# resonant-bpf-rev3.net
KiCad netlist of a schematic drawn in EAGLE
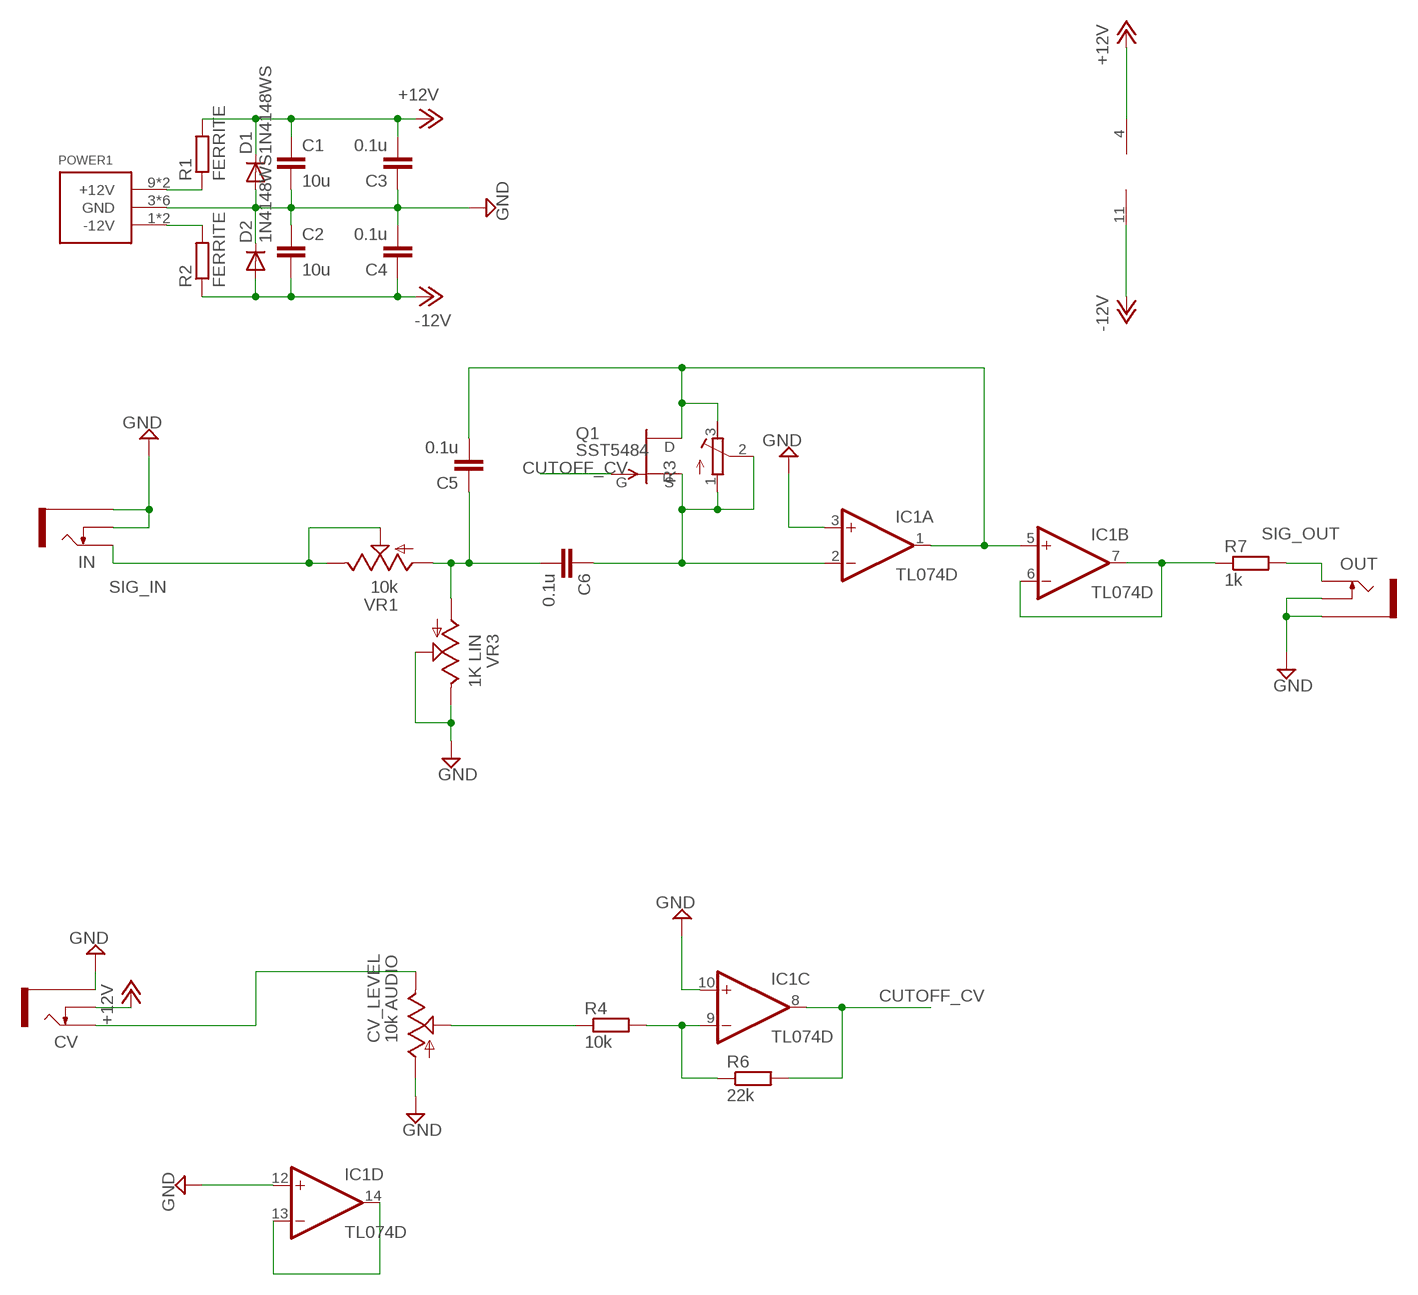
[diagram p0: schematic, sheet 1]

(export (version "E")
  (design (tool "Eeschema 10.0.6"))
  (components
    (comp (ref "C1")
      (value "10u")
      (footprint "eagle-import:C0805")
      (libsource (lib "eagle-import") (part "C-EUC0805"))
    )
    (comp (ref "C2")
      (value "10u")
      (footprint "eagle-import:C0805")
      (libsource (lib "eagle-import") (part "C-EUC0805"))
    )
    (comp (ref "C3")
      (value "0.1u")
      (footprint "eagle-import:C0805")
      (libsource (lib "eagle-import") (part "C-EUC0805"))
    )
    (comp (ref "C4")
      (value "0.1u")
      (footprint "eagle-import:C0805")
      (libsource (lib "eagle-import") (part "C-EUC0805"))
    )
    (comp (ref "C5")
      (value "0.1u")
      (footprint "eagle-import:C0805")
      (libsource (lib "eagle-import") (part "C-EUC0805"))
    )
    (comp (ref "C6")
      (value "0.1u")
      (footprint "eagle-import:C0805")
      (libsource (lib "eagle-import") (part "C-EUC0805"))
    )
    (comp (ref "CV")
      (value "THONKICONNNEW")
      (footprint "eagle-import:WQP-PJ301M-12_JACK")
      (libsource (lib "eagle-import") (part "THONKICONNNEW"))
    )
    (comp (ref "CV_LEVEL")
      (value "10k AUDIO")
      (footprint "eagle-import:9MM_SNAP-IN_POT")
      (libsource (lib "eagle-import") (part "9MM_SNAP-IN_POT_"))
    )
    (comp (ref "D1")
      (value "1N4148WS")
      (footprint "eagle-import:SOD323-W")
      (libsource (lib "eagle-import") (part "DIODE-SOD323-W"))
    )
    (comp (ref "D2")
      (value "1N4148WS")
      (footprint "eagle-import:SOD323-W")
      (libsource (lib "eagle-import") (part "DIODE-SOD323-W"))
    )
    (comp (ref "IC1")
      (value "TL074D")
      (footprint "eagle-import:SO14")
      (libsource (lib "eagle-import") (part "TL074D"))
    )
    (comp (ref "IN")
      (value "THONKICONNNEW")
      (footprint "eagle-import:WQP-PJ301M-12_JACK")
      (libsource (lib "eagle-import") (part "THONKICONNNEW"))
    )
    (comp (ref "OUT")
      (value "THONKICONNNEW")
      (footprint "eagle-import:WQP-PJ301M-12_JACK")
      (libsource (lib "eagle-import") (part "THONKICONNNEW"))
    )
    (comp (ref "POWER1")
      (value "POWER_SIMPLE10")
      (footprint "eagle-import:POWER_10")
      (libsource (lib "eagle-import") (part "POWER_SIMPLE10"))
    )
    (comp (ref "Q1")
      (value "SST5484")
      (footprint "eagle-import:SOT23")
      (libsource (lib "eagle-import") (part "?548SST4"))
    )
    (comp (ref "R1")
      (value "FERRITE")
      (footprint "eagle-import:R0805")
      (libsource (lib "eagle-import") (part "R-EU_R0805"))
    )
    (comp (ref "R2")
      (value "FERRITE")
      (footprint "eagle-import:R0805")
      (libsource (lib "eagle-import") (part "R-EU_R0805"))
    )
    (comp (ref "R3")
      (value "R-TRIMM3296W")
      (footprint "eagle-import:RTRIM3296W")
      (libsource (lib "eagle-import") (part "R-TRIMM3296W"))
    )
    (comp (ref "R4")
      (value "10k")
      (footprint "eagle-import:R0805")
      (libsource (lib "eagle-import") (part "R-EU_R0805"))
    )
    (comp (ref "R6")
      (value "22k")
      (footprint "eagle-import:R0805")
      (libsource (lib "eagle-import") (part "R-EU_R0805"))
    )
    (comp (ref "R7")
      (value "1k")
      (footprint "eagle-import:R0805")
      (libsource (lib "eagle-import") (part "R-EU_R0805"))
    )
    (comp (ref "VR1")
      (value "10k")
      (footprint "eagle-import:9MM_SNAP-IN_POT")
      (libsource (lib "eagle-import") (part "9MM_SNAP-IN_POT_"))
    )
    (comp (ref "VR3")
      (value "1K LIN")
      (footprint "eagle-import:9MM_SNAP-IN_POT")
      (libsource (lib "eagle-import") (part "9MM_SNAP-IN_POT_"))
    )
  )
  (nets
    (net (code "1") (name "+12V") (class "Default")
      (node (ref "C1") (pin "1") (pinfunction "1_1") (pintype "passive"))
      (node (ref "C3") (pin "2") (pinfunction "2_2") (pintype "passive"))
      (node (ref "CV") (pin "P$2_SWITCH") (pinfunction "SWITCH_P$2_SWITCH") (pintype "passive"))
      (node (ref "D1") (pin "C") (pinfunction "C_C") (pintype "passive"))
      (node (ref "IC1") (pin "4") (pinfunction "V+_4") (pintype "power_in"))
      (node (ref "R1") (pin "2") (pinfunction "2_2") (pintype "passive"))
    )
    (net (code "2") (name "-12V") (class "Default")
      (node (ref "C2") (pin "2") (pinfunction "2_2") (pintype "passive"))
      (node (ref "C4") (pin "1") (pinfunction "1_1") (pintype "passive"))
      (node (ref "D2") (pin "A") (pinfunction "A_A") (pintype "passive"))
      (node (ref "IC1") (pin "11") (pinfunction "V-_11") (pintype "power_in"))
      (node (ref "R2") (pin "1") (pinfunction "1_1") (pintype "passive"))
    )
    (net (code "3") (name "/CUTOFF_CV") (class "Default")
      (node (ref "IC1") (pin "8") (pinfunction "OUT_8") (pintype "output"))
      (node (ref "Q1") (pin "3") (pinfunction "G_3") (pintype "passive"))
      (node (ref "R6") (pin "2") (pinfunction "2_2") (pintype "passive"))
    )
    (net (code "4") (name "/SIG_IN") (class "Default")
      (node (ref "IN") (pin "P$1_TIP") (pinfunction "TIP_P$1_TIP") (pintype "passive"))
      (node (ref "VR1") (pin "2") (pinfunction "S_2") (pintype "passive"))
      (node (ref "VR1") (pin "3") (pinfunction "E_3") (pintype "passive"))
    )
    (net (code "5") (name "/SIG_OUT") (class "Default")
      (node (ref "OUT") (pin "P$1_TIP") (pinfunction "TIP_P$1_TIP") (pintype "passive"))
      (node (ref "R7") (pin "2") (pinfunction "2_2") (pintype "passive"))
    )
    (net (code "6") (name "GND") (class "Default")
      (node (ref "C1") (pin "2") (pinfunction "2_2") (pintype "passive"))
      (node (ref "C2") (pin "1") (pinfunction "1_1") (pintype "passive"))
      (node (ref "C3") (pin "1") (pinfunction "1_1") (pintype "passive"))
      (node (ref "C4") (pin "2") (pinfunction "2_2") (pintype "passive"))
      (node (ref "CV") (pin "P$3_SLEEVE") (pinfunction "SLEEVE_P$3_SLEEVE") (pintype "passive"))
      (node (ref "CV_LEVEL") (pin "1") (pinfunction "A_1") (pintype "passive"))
      (node (ref "D1") (pin "A") (pinfunction "A_A") (pintype "passive"))
      (node (ref "D2") (pin "C") (pinfunction "C_C") (pintype "passive"))
      (node (ref "IC1") (pin "10") (pinfunction "+IN_10") (pintype "input"))
      (node (ref "IC1") (pin "12") (pinfunction "+IN_12") (pintype "input"))
      (node (ref "IC1") (pin "3") (pinfunction "+IN_3") (pintype "input"))
      (node (ref "IN") (pin "P$2_SWITCH") (pinfunction "SWITCH_P$2_SWITCH") (pintype "passive"))
      (node (ref "IN") (pin "P$3_SLEEVE") (pinfunction "SLEEVE_P$3_SLEEVE") (pintype "passive"))
      (node (ref "OUT") (pin "P$2_SWITCH") (pinfunction "SWITCH_P$2_SWITCH") (pintype "passive"))
      (node (ref "OUT") (pin "P$3_SLEEVE") (pinfunction "SLEEVE_P$3_SLEEVE") (pintype "passive"))
      (node (ref "POWER1") (pin "3") (pinfunction "GND_3") (pintype "bidirectional"))
      (node (ref "POWER1") (pin "4") (pinfunction "GND_4") (pintype "bidirectional"))
      (node (ref "POWER1") (pin "5") (pinfunction "GND_5") (pintype "bidirectional"))
      (node (ref "POWER1") (pin "6") (pinfunction "GND_6") (pintype "bidirectional"))
      (node (ref "POWER1") (pin "7") (pinfunction "GND_7") (pintype "bidirectional"))
      (node (ref "POWER1") (pin "8") (pinfunction "GND_8") (pintype "bidirectional"))
      (node (ref "VR3") (pin "2") (pinfunction "S_2") (pintype "passive"))
      (node (ref "VR3") (pin "3") (pinfunction "E_3") (pintype "passive"))
    )
    (net (code "7") (name "Net-(CV-TIP)") (class "Default")
      (node (ref "CV") (pin "P$1_TIP") (pinfunction "TIP_P$1_TIP") (pintype "passive"))
      (node (ref "CV_LEVEL") (pin "3") (pinfunction "E_3") (pintype "passive"))
    )
    (net (code "8") (name "Net-(CV_LEVEL-S)") (class "Default")
      (node (ref "CV_LEVEL") (pin "2") (pinfunction "S_2") (pintype "passive"))
      (node (ref "R4") (pin "1") (pinfunction "1_1") (pintype "passive"))
    )
    (net (code "9") (name "Net-(IC1A--IN)") (class "Default")
      (node (ref "C6") (pin "1") (pinfunction "1_1") (pintype "passive"))
      (node (ref "IC1") (pin "2") (pinfunction "-IN_2") (pintype "input"))
      (node (ref "Q1") (pin "2") (pinfunction "S_2") (pintype "passive"))
      (node (ref "R3") (pin "1") (pinfunction "A_1") (pintype "passive"))
      (node (ref "R3") (pin "2") (pinfunction "S_2") (pintype "passive"))
    )
    (net (code "10") (name "Net-(IC1A-OUT)") (class "Default")
      (node (ref "C5") (pin "2") (pinfunction "2_2") (pintype "passive"))
      (node (ref "IC1") (pin "1") (pinfunction "OUT_1") (pintype "output"))
      (node (ref "IC1") (pin "5") (pinfunction "+IN_5") (pintype "input"))
      (node (ref "Q1") (pin "1") (pinfunction "D_1") (pintype "passive"))
      (node (ref "R3") (pin "3") (pinfunction "E_3") (pintype "passive"))
    )
    (net (code "11") (name "Net-(IC1B--IN)") (class "Default")
      (node (ref "IC1") (pin "6") (pinfunction "-IN_6") (pintype "input"))
      (node (ref "IC1") (pin "7") (pinfunction "OUT_7") (pintype "output"))
      (node (ref "R7") (pin "1") (pinfunction "1_1") (pintype "passive"))
    )
    (net (code "12") (name "Net-(IC1C--IN)") (class "Default")
      (node (ref "IC1") (pin "9") (pinfunction "-IN_9") (pintype "input"))
      (node (ref "R4") (pin "2") (pinfunction "2_2") (pintype "passive"))
      (node (ref "R6") (pin "1") (pinfunction "1_1") (pintype "passive"))
    )
    (net (code "13") (name "Net-(IC1D--IN)") (class "Default")
      (node (ref "IC1") (pin "13") (pinfunction "-IN_13") (pintype "input"))
      (node (ref "IC1") (pin "14") (pinfunction "OUT_14") (pintype "output"))
    )
    (net (code "14") (name "Net-(POWER1-+12V-Pad10)") (class "Default")
      (node (ref "POWER1") (pin "10") (pinfunction "+12V_10") (pintype "bidirectional"))
      (node (ref "POWER1") (pin "9") (pinfunction "+12V_9") (pintype "bidirectional"))
      (node (ref "R1") (pin "1") (pinfunction "1_1") (pintype "passive"))
    )
    (net (code "15") (name "Net-(POWER1--12V-Pad1)") (class "Default")
      (node (ref "POWER1") (pin "1") (pinfunction "-12V_1") (pintype "bidirectional"))
      (node (ref "POWER1") (pin "2") (pinfunction "-12V_2") (pintype "bidirectional"))
      (node (ref "R2") (pin "2") (pinfunction "2_2") (pintype "passive"))
    )
    (net (code "16") (name "Net-(VR1-A)") (class "Default")
      (node (ref "C5") (pin "1") (pinfunction "1_1") (pintype "passive"))
      (node (ref "C6") (pin "2") (pinfunction "2_2") (pintype "passive"))
      (node (ref "VR1") (pin "1") (pinfunction "A_1") (pintype "passive"))
      (node (ref "VR3") (pin "1") (pinfunction "A_1") (pintype "passive"))
    )
  )
)
